# bluetooth.net
KiCad netlist of a schematic drawn in Altium Designer
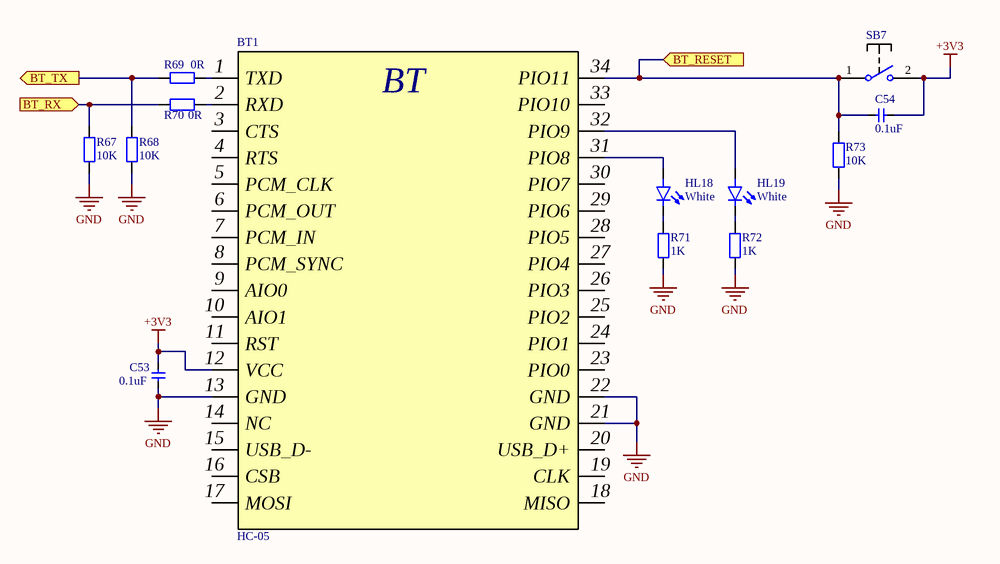
[diagram p0: bluetooth.SchDoc]

(export (version "E")
  (design (tool "Eeschema 10.0.6"))
  (components
    (comp (ref "BT1")
      (value "HC-05")
      (footprint "HC-05")
      (description "Bluetooth HC-05")
      (libsource (lib "Asterisk") (part "HC-05"))
    )
    (comp (ref "C53")
      (value "0.1uF")
      (footprint "CAP0805")
      (description "Ceramic SMD Cap")
      (libsource (lib "Asterisk") (part "CAP Ceramic"))
    )
    (comp (ref "C54")
      (value "0.1uF")
      (footprint "CAP0805")
      (description "Ceramic SMD Cap")
      (libsource (lib "Asterisk") (part "CAP Ceramic"))
    )
    (comp (ref "HL18")
      (value "White")
      (footprint "LED0603_WHITE")
      (description "LED smd")
      (libsource (lib "Asterisk") (part "LED"))
    )
    (comp (ref "HL19")
      (value "White")
      (footprint "LED0603_WHITE")
      (description "LED smd")
      (libsource (lib "Asterisk") (part "LED"))
    )
    (comp (ref "R67")
      (value "10K")
      (footprint "RES0805")
      (description "RES smd")
      (libsource (lib "Asterisk") (part "RES"))
    )
    (comp (ref "R68")
      (value "10K")
      (footprint "RES0805")
      (description "RES smd")
      (libsource (lib "Asterisk") (part "RES"))
    )
    (comp (ref "R69")
      (value "0R")
      (footprint "RES0805")
      (description "RES smd")
      (libsource (lib "Asterisk") (part "RES"))
    )
    (comp (ref "R70")
      (value "0R")
      (footprint "RES0805")
      (description "RES smd")
      (libsource (lib "Asterisk") (part "RES"))
    )
    (comp (ref "R71")
      (value "1K")
      (footprint "RES0805")
      (description "RES smd")
      (libsource (lib "Asterisk") (part "RES"))
    )
    (comp (ref "R72")
      (value "1K")
      (footprint "RES0805")
      (description "RES smd")
      (libsource (lib "Asterisk") (part "RES"))
    )
    (comp (ref "R73")
      (value "10K")
      (footprint "RES0805")
      (description "RES smd")
      (libsource (lib "Asterisk") (part "RES"))
    )
    (comp (ref "SB7")
      (value "PTS636 SP43 LFS")
      (footprint "PTS636 SP43 LFS")
      (description "TACT 6.0 X 3.5, 4.3 MM H, 320GF,")
      (fields (field (name "DIGI-KEY PART NUMBER") "CKN12304-ND"))
      (libsource (lib "SssAccesDatbase") (part "SW-SPST"))
    )
  )
  (nets
    (net (code "1") (name "+3V3") (class "Default")
      (node (ref "BT1") (pin "12") (pinfunction "VCC_12") (pintype "passive"))
      (node (ref "C53") (pin "2") (pinfunction "2_2") (pintype "passive"))
      (node (ref "C54") (pin "1") (pinfunction "1_1") (pintype "passive"))
      (node (ref "SB7") (pin "2") (pinfunction "NO_2") (pintype "passive"))
    )
    (net (code "2") (name "/BT_RESET") (class "Default")
      (node (ref "BT1") (pin "34") (pinfunction "PIO11_34") (pintype "passive"))
      (node (ref "C54") (pin "2") (pinfunction "2_2") (pintype "passive"))
      (node (ref "R73") (pin "2") (pinfunction "2_2") (pintype "passive"))
      (node (ref "SB7") (pin "1") (pinfunction "COMMON_1") (pintype "passive"))
    )
    (net (code "3") (name "/BT_RX") (class "Default")
      (node (ref "R67") (pin "2") (pinfunction "2_2") (pintype "passive"))
      (node (ref "R70") (pin "2") (pinfunction "2_2") (pintype "passive"))
    )
    (net (code "4") (name "/BT_TX") (class "Default")
      (node (ref "R68") (pin "2") (pinfunction "2_2") (pintype "passive"))
      (node (ref "R69") (pin "2") (pinfunction "2_2") (pintype "passive"))
    )
    (net (code "5") (name "GND") (class "Default")
      (node (ref "BT1") (pin "13") (pinfunction "GND_13") (pintype "passive"))
      (node (ref "BT1") (pin "21") (pinfunction "GND_21") (pintype "passive"))
      (node (ref "BT1") (pin "22") (pinfunction "GND_22") (pintype "passive"))
      (node (ref "C53") (pin "1") (pinfunction "1_1") (pintype "passive"))
      (node (ref "R67") (pin "1") (pinfunction "1_1") (pintype "passive"))
      (node (ref "R68") (pin "1") (pinfunction "1_1") (pintype "passive"))
      (node (ref "R71") (pin "1") (pinfunction "1_1") (pintype "passive"))
      (node (ref "R72") (pin "1") (pinfunction "1_1") (pintype "passive"))
      (node (ref "R73") (pin "1") (pinfunction "1_1") (pintype "passive"))
    )
    (net (code "6") (name "Net-(BT1-PIO8)") (class "Default")
      (node (ref "BT1") (pin "31") (pinfunction "PIO8_31") (pintype "passive"))
      (node (ref "HL18") (pin "2") (pinfunction "A_2") (pintype "passive"))
    )
    (net (code "7") (name "Net-(BT1-PIO9)") (class "Default")
      (node (ref "BT1") (pin "32") (pinfunction "PIO9_32") (pintype "passive"))
      (node (ref "HL19") (pin "2") (pinfunction "A_2") (pintype "passive"))
    )
    (net (code "8") (name "Net-(BT1-RXD)") (class "Default")
      (node (ref "BT1") (pin "2") (pinfunction "RXD_2") (pintype "passive"))
      (node (ref "R70") (pin "1") (pinfunction "1_1") (pintype "passive"))
    )
    (net (code "9") (name "Net-(BT1-TXD)") (class "Default")
      (node (ref "BT1") (pin "1") (pinfunction "TXD_1") (pintype "passive"))
      (node (ref "R69") (pin "1") (pinfunction "1_1") (pintype "passive"))
    )
    (net (code "10") (name "Net-(HL18-K)") (class "Default")
      (node (ref "HL18") (pin "1") (pinfunction "K_1") (pintype "passive"))
      (node (ref "R71") (pin "2") (pinfunction "2_2") (pintype "passive"))
    )
    (net (code "11") (name "Net-(HL19-K)") (class "Default")
      (node (ref "HL19") (pin "1") (pinfunction "K_1") (pintype "passive"))
      (node (ref "R72") (pin "2") (pinfunction "2_2") (pintype "passive"))
    )
    (net (code "12") (name "unconnected-(BT1-AIO0-Pad9)") (class "Default")
      (node (ref "BT1") (pin "9") (pinfunction "AIO0_9") (pintype "passive"))
    )
    (net (code "13") (name "unconnected-(BT1-AIO1-Pad10)") (class "Default")
      (node (ref "BT1") (pin "10") (pinfunction "AIO1_10") (pintype "passive"))
    )
    (net (code "14") (name "unconnected-(BT1-CLK-Pad19)") (class "Default")
      (node (ref "BT1") (pin "19") (pinfunction "CLK_19") (pintype "passive"))
    )
    (net (code "15") (name "unconnected-(BT1-CSB-Pad16)") (class "Default")
      (node (ref "BT1") (pin "16") (pinfunction "CSB_16") (pintype "passive"))
    )
    (net (code "16") (name "unconnected-(BT1-CTS-Pad3)") (class "Default")
      (node (ref "BT1") (pin "3") (pinfunction "CTS_3") (pintype "passive"))
    )
    (net (code "17") (name "unconnected-(BT1-MISO-Pad18)") (class "Default")
      (node (ref "BT1") (pin "18") (pinfunction "MISO_18") (pintype "passive"))
    )
    (net (code "18") (name "unconnected-(BT1-MOSI-Pad17)") (class "Default")
      (node (ref "BT1") (pin "17") (pinfunction "MOSI_17") (pintype "passive"))
    )
    (net (code "19") (name "unconnected-(BT1-NC-Pad14)") (class "Default")
      (node (ref "BT1") (pin "14") (pinfunction "NC_14") (pintype "passive"))
    )
    (net (code "20") (name "unconnected-(BT1-PCM_CLK-Pad5)") (class "Default")
      (node (ref "BT1") (pin "5") (pinfunction "PCM_CLK_5") (pintype "passive"))
    )
    (net (code "21") (name "unconnected-(BT1-PCM_IN-Pad7)") (class "Default")
      (node (ref "BT1") (pin "7") (pinfunction "PCM_IN_7") (pintype "passive"))
    )
    (net (code "22") (name "unconnected-(BT1-PCM_OUT-Pad6)") (class "Default")
      (node (ref "BT1") (pin "6") (pinfunction "PCM_OUT_6") (pintype "passive"))
    )
    (net (code "23") (name "unconnected-(BT1-PCM_SYNC-Pad8)") (class "Default")
      (node (ref "BT1") (pin "8") (pinfunction "PCM_SYNC_8") (pintype "passive"))
    )
    (net (code "24") (name "unconnected-(BT1-PIO0-Pad23)") (class "Default")
      (node (ref "BT1") (pin "23") (pinfunction "PIO0_23") (pintype "passive"))
    )
    (net (code "25") (name "unconnected-(BT1-PIO1-Pad24)") (class "Default")
      (node (ref "BT1") (pin "24") (pinfunction "PIO1_24") (pintype "passive"))
    )
    (net (code "26") (name "unconnected-(BT1-PIO2-Pad25)") (class "Default")
      (node (ref "BT1") (pin "25") (pinfunction "PIO2_25") (pintype "passive"))
    )
    (net (code "27") (name "unconnected-(BT1-PIO3-Pad26)") (class "Default")
      (node (ref "BT1") (pin "26") (pinfunction "PIO3_26") (pintype "passive"))
    )
    (net (code "28") (name "unconnected-(BT1-PIO4-Pad27)") (class "Default")
      (node (ref "BT1") (pin "27") (pinfunction "PIO4_27") (pintype "passive"))
    )
    (net (code "29") (name "unconnected-(BT1-PIO5-Pad28)") (class "Default")
      (node (ref "BT1") (pin "28") (pinfunction "PIO5_28") (pintype "passive"))
    )
    (net (code "30") (name "unconnected-(BT1-PIO6-Pad29)") (class "Default")
      (node (ref "BT1") (pin "29") (pinfunction "PIO6_29") (pintype "passive"))
    )
    (net (code "31") (name "unconnected-(BT1-PIO7-Pad30)") (class "Default")
      (node (ref "BT1") (pin "30") (pinfunction "PIO7_30") (pintype "passive"))
    )
    (net (code "32") (name "unconnected-(BT1-PIO10-Pad33)") (class "Default")
      (node (ref "BT1") (pin "33") (pinfunction "PIO10_33") (pintype "passive"))
    )
    (net (code "33") (name "unconnected-(BT1-RST-Pad11)") (class "Default")
      (node (ref "BT1") (pin "11") (pinfunction "RST_11") (pintype "passive"))
    )
    (net (code "34") (name "unconnected-(BT1-RTS-Pad4)") (class "Default")
      (node (ref "BT1") (pin "4") (pinfunction "RTS_4") (pintype "passive"))
    )
    (net (code "35") (name "unconnected-(BT1-USB_D+-Pad20)") (class "Default")
      (node (ref "BT1") (pin "20") (pinfunction "USB_D+_20") (pintype "passive"))
    )
    (net (code "36") (name "unconnected-(BT1-USB_D--Pad15)") (class "Default")
      (node (ref "BT1") (pin "15") (pinfunction "USB_D-_15") (pintype "passive"))
    )
  )
)
